# probe.net
KiCad netlist of a schematic drawn in EAGLE
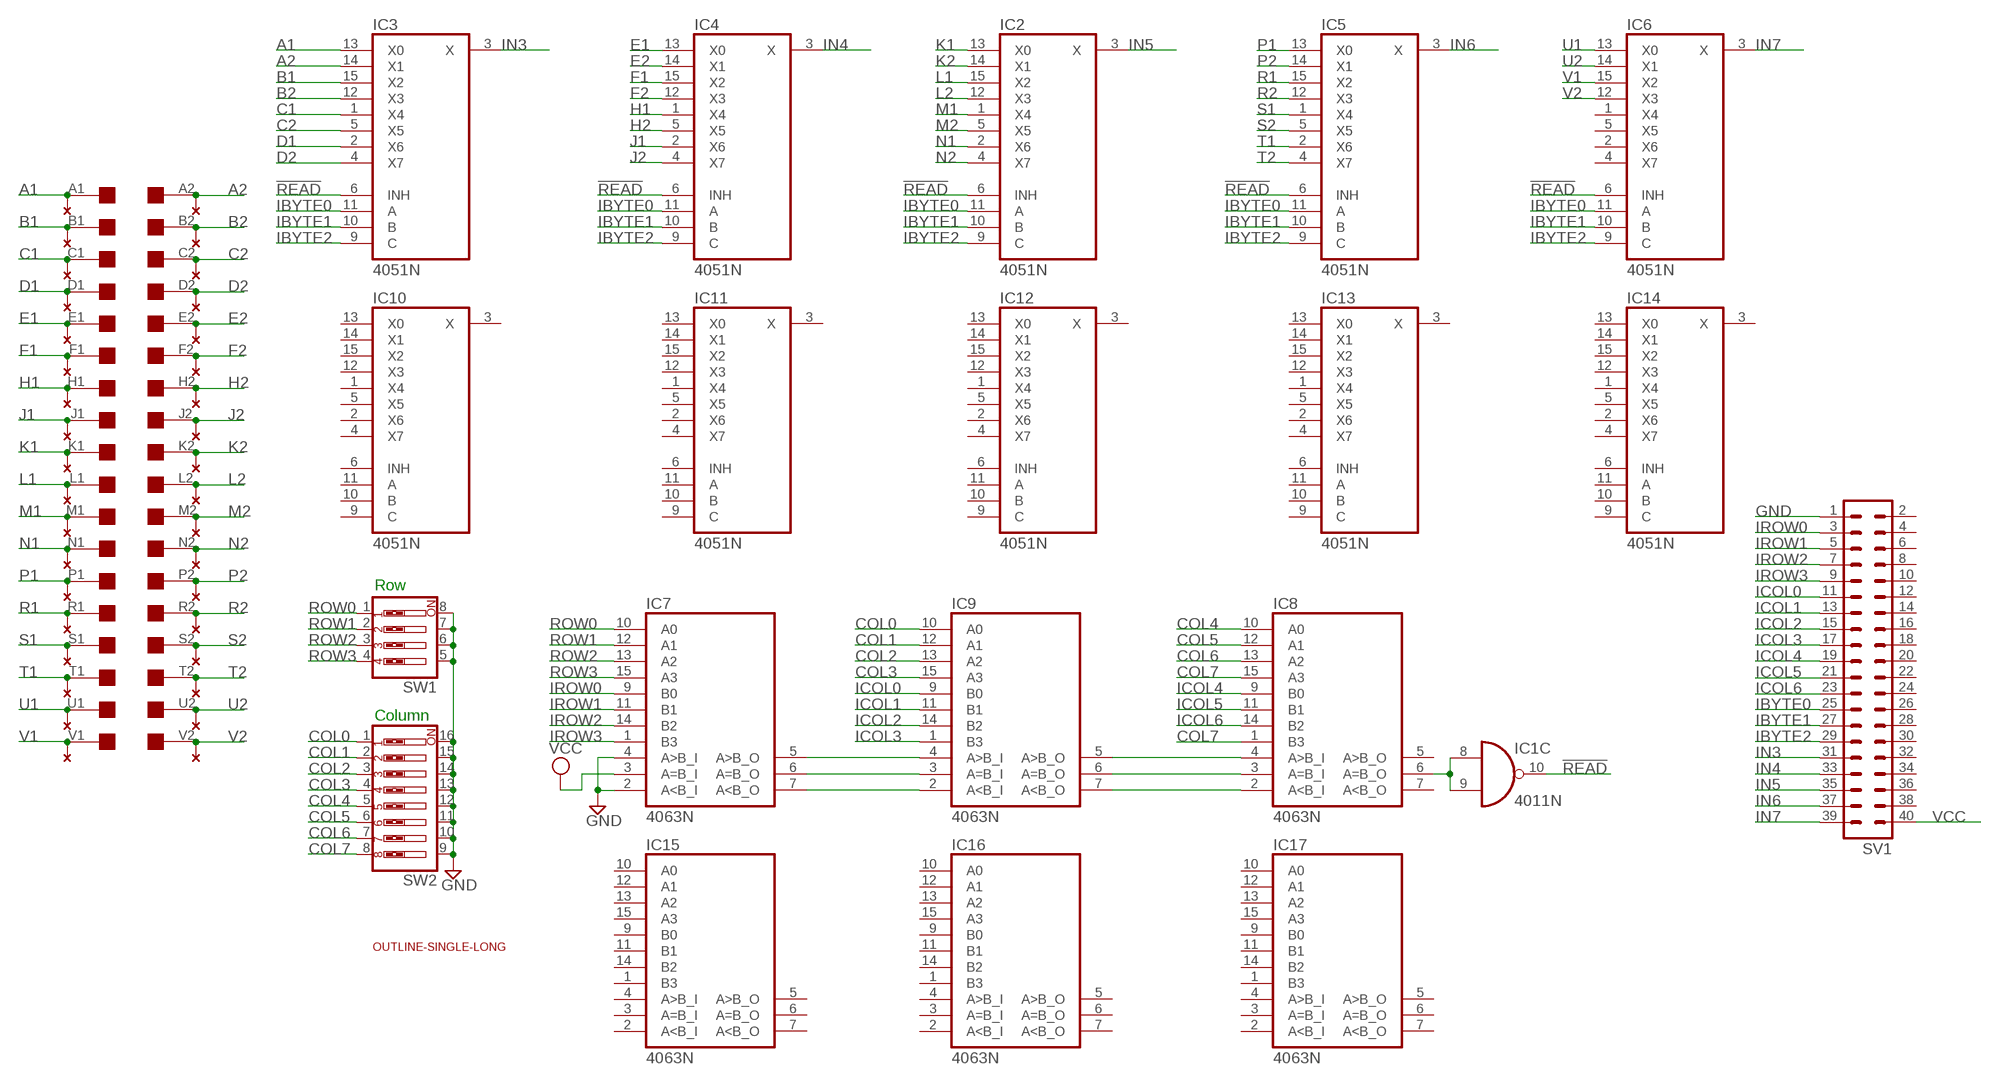
[diagram p0: schematic, sheet 1]

(export (version "E")
  (design (tool "Eeschema 10.0.6"))
  (components
    (comp (ref "EDGE1")
      (value "EDGE-2CONNECTOR")
      (footprint "eagle-import:EDGE-CON2")
      (libsource (lib "eagle-import") (part "EDGE-2CONNECTOR"))
    )
    (comp (ref "IC1")
      (value "4011N")
      (footprint "eagle-import:DIL14")
      (libsource (lib "eagle-import") (part "4011N"))
    )
    (comp (ref "IC2")
      (value "4051N")
      (footprint "eagle-import:DIL16")
      (libsource (lib "eagle-import") (part "4051N"))
    )
    (comp (ref "IC3")
      (value "4051N")
      (footprint "eagle-import:DIL16")
      (libsource (lib "eagle-import") (part "4051N"))
    )
    (comp (ref "IC4")
      (value "4051N")
      (footprint "eagle-import:DIL16")
      (libsource (lib "eagle-import") (part "4051N"))
    )
    (comp (ref "IC5")
      (value "4051N")
      (footprint "eagle-import:DIL16")
      (libsource (lib "eagle-import") (part "4051N"))
    )
    (comp (ref "IC6")
      (value "4051N")
      (footprint "eagle-import:DIL16")
      (libsource (lib "eagle-import") (part "4051N"))
    )
    (comp (ref "IC7")
      (value "4063N")
      (footprint "eagle-import:DIL16")
      (libsource (lib "eagle-import") (part "4063N"))
    )
    (comp (ref "IC8")
      (value "4063N")
      (footprint "eagle-import:DIL16")
      (libsource (lib "eagle-import") (part "4063N"))
    )
    (comp (ref "IC9")
      (value "4063N")
      (footprint "eagle-import:DIL16")
      (libsource (lib "eagle-import") (part "4063N"))
    )
    (comp (ref "IC10")
      (value "4051N")
      (footprint "eagle-import:DIL16")
      (libsource (lib "eagle-import") (part "4051N"))
    )
    (comp (ref "IC11")
      (value "4051N")
      (footprint "eagle-import:DIL16")
      (libsource (lib "eagle-import") (part "4051N"))
    )
    (comp (ref "IC12")
      (value "4051N")
      (footprint "eagle-import:DIL16")
      (libsource (lib "eagle-import") (part "4051N"))
    )
    (comp (ref "IC13")
      (value "4051N")
      (footprint "eagle-import:DIL16")
      (libsource (lib "eagle-import") (part "4051N"))
    )
    (comp (ref "IC14")
      (value "4051N")
      (footprint "eagle-import:DIL16")
      (libsource (lib "eagle-import") (part "4051N"))
    )
    (comp (ref "IC15")
      (value "4063N")
      (footprint "eagle-import:DIL16")
      (libsource (lib "eagle-import") (part "4063N"))
    )
    (comp (ref "IC16")
      (value "4063N")
      (footprint "eagle-import:DIL16")
      (libsource (lib "eagle-import") (part "4063N"))
    )
    (comp (ref "IC17")
      (value "4063N")
      (footprint "eagle-import:DIL16")
      (libsource (lib "eagle-import") (part "4063N"))
    )
    (comp (ref "SV1")
      (value "MA20-2")
      (footprint "eagle-import:MA20-2")
      (libsource (lib "eagle-import") (part "MA20-2"))
    )
    (comp (ref "SW1")
      (value "SW_DIP-4")
      (footprint "eagle-import:EDG-04")
      (libsource (lib "eagle-import") (part "SW_DIP-4"))
    )
    (comp (ref "SW2")
      (value "SW_DIP-8")
      (footprint "eagle-import:EDG-08")
      (libsource (lib "eagle-import") (part "SW_DIP-8"))
    )
    (comp (ref "U$1")
      (value "OUTLINE-SINGLE-LONG")
      (footprint "eagle-import:SINGLE-LONG")
      (libsource (lib "eagle-import") (part "OUTLINE-SINGLE-LONG"))
    )
    (comp (ref "U$3")
      (value "THRU-HOLE2")
      (footprint "eagle-import:THRU-HOLEB")
      (libsource (lib "eagle-import") (part "THRU-HOLE2"))
    )
  )
  (nets
    (net (code "1") (name "/A1") (class "Default")
      (node (ref "EDGE1") (pin "A1") (pinfunction "1_A1") (pintype "bidirectional"))
      (node (ref "IC3") (pin "13") (pinfunction "X0_13") (pintype "bidirectional"))
      (node (ref "U$3") (pin "A1") (pinfunction "P$1_A1") (pintype "passive"))
    )
    (net (code "2") (name "/A2") (class "Default")
      (node (ref "EDGE1") (pin "A2") (pinfunction "1_A2") (pintype "bidirectional"))
      (node (ref "IC3") (pin "14") (pinfunction "X1_14") (pintype "bidirectional"))
      (node (ref "U$3") (pin "A2") (pinfunction "P$1_A2") (pintype "passive"))
    )
    (net (code "3") (name "/B1") (class "Default")
      (node (ref "EDGE1") (pin "B1") (pinfunction "1_B1") (pintype "bidirectional"))
      (node (ref "IC3") (pin "15") (pinfunction "X2_15") (pintype "bidirectional"))
      (node (ref "U$3") (pin "B1") (pinfunction "P$1_B1") (pintype "passive"))
    )
    (net (code "4") (name "/B2") (class "Default")
      (node (ref "EDGE1") (pin "B2") (pinfunction "1_B2") (pintype "bidirectional"))
      (node (ref "IC3") (pin "12") (pinfunction "X3_12") (pintype "bidirectional"))
      (node (ref "U$3") (pin "B2") (pinfunction "P$1_B2") (pintype "passive"))
    )
    (net (code "5") (name "/C1") (class "Default")
      (node (ref "EDGE1") (pin "C1") (pinfunction "1_C1") (pintype "bidirectional"))
      (node (ref "IC3") (pin "1") (pinfunction "X4_1") (pintype "bidirectional"))
      (node (ref "U$3") (pin "C1") (pinfunction "P$1_C1") (pintype "passive"))
    )
    (net (code "6") (name "/C2") (class "Default")
      (node (ref "EDGE1") (pin "C2") (pinfunction "1_C2") (pintype "bidirectional"))
      (node (ref "IC3") (pin "5") (pinfunction "X5_5") (pintype "bidirectional"))
      (node (ref "U$3") (pin "C2") (pinfunction "P$1_C2") (pintype "passive"))
    )
    (net (code "7") (name "/COL0") (class "Default")
      (node (ref "IC9") (pin "10") (pinfunction "A0_10") (pintype "input"))
      (node (ref "SW2") (pin "1") (pinfunction "1_1") (pintype "passive"))
    )
    (net (code "8") (name "/COL1") (class "Default")
      (node (ref "IC9") (pin "12") (pinfunction "A1_12") (pintype "input"))
      (node (ref "SW2") (pin "2") (pinfunction "2_2") (pintype "passive"))
    )
    (net (code "9") (name "/COL2") (class "Default")
      (node (ref "IC9") (pin "13") (pinfunction "A2_13") (pintype "input"))
      (node (ref "SW2") (pin "3") (pinfunction "3_3") (pintype "passive"))
    )
    (net (code "10") (name "/COL3") (class "Default")
      (node (ref "IC9") (pin "15") (pinfunction "A3_15") (pintype "input"))
      (node (ref "SW2") (pin "4") (pinfunction "4_4") (pintype "passive"))
    )
    (net (code "11") (name "/COL4") (class "Default")
      (node (ref "IC8") (pin "10") (pinfunction "A0_10") (pintype "input"))
      (node (ref "SW2") (pin "5") (pinfunction "5_5") (pintype "passive"))
    )
    (net (code "12") (name "/COL5") (class "Default")
      (node (ref "IC8") (pin "12") (pinfunction "A1_12") (pintype "input"))
      (node (ref "SW2") (pin "6") (pinfunction "6_6") (pintype "passive"))
    )
    (net (code "13") (name "/COL6") (class "Default")
      (node (ref "IC8") (pin "13") (pinfunction "A2_13") (pintype "input"))
      (node (ref "SW2") (pin "7") (pinfunction "7_7") (pintype "passive"))
    )
    (net (code "14") (name "/COL7") (class "Default")
      (node (ref "IC8") (pin "1") (pinfunction "B3_1") (pintype "input"))
      (node (ref "IC8") (pin "15") (pinfunction "A3_15") (pintype "input"))
      (node (ref "SW2") (pin "8") (pinfunction "8_8") (pintype "passive"))
    )
    (net (code "15") (name "/D1") (class "Default")
      (node (ref "EDGE1") (pin "D1") (pinfunction "1_D1") (pintype "bidirectional"))
      (node (ref "IC3") (pin "2") (pinfunction "X6_2") (pintype "bidirectional"))
      (node (ref "U$3") (pin "D1") (pinfunction "P$1_D1") (pintype "passive"))
    )
    (net (code "16") (name "/D2") (class "Default")
      (node (ref "EDGE1") (pin "D2") (pinfunction "1_D2") (pintype "bidirectional"))
      (node (ref "IC3") (pin "4") (pinfunction "X7_4") (pintype "bidirectional"))
      (node (ref "U$3") (pin "D2") (pinfunction "P$1_D2") (pintype "passive"))
    )
    (net (code "17") (name "/E1") (class "Default")
      (node (ref "EDGE1") (pin "E1") (pinfunction "1_E1") (pintype "bidirectional"))
      (node (ref "IC4") (pin "13") (pinfunction "X0_13") (pintype "bidirectional"))
      (node (ref "U$3") (pin "E1") (pinfunction "P$1_E1") (pintype "passive"))
    )
    (net (code "18") (name "/E2") (class "Default")
      (node (ref "EDGE1") (pin "E2") (pinfunction "1_E2") (pintype "bidirectional"))
      (node (ref "IC4") (pin "14") (pinfunction "X1_14") (pintype "bidirectional"))
      (node (ref "U$3") (pin "E2") (pinfunction "P$1_E2") (pintype "passive"))
    )
    (net (code "19") (name "/F1") (class "Default")
      (node (ref "EDGE1") (pin "F1") (pinfunction "1_F1") (pintype "bidirectional"))
      (node (ref "IC4") (pin "15") (pinfunction "X2_15") (pintype "bidirectional"))
      (node (ref "U$3") (pin "F1") (pinfunction "P$1_F1") (pintype "passive"))
    )
    (net (code "20") (name "/F2") (class "Default")
      (node (ref "EDGE1") (pin "F2") (pinfunction "1_F2") (pintype "bidirectional"))
      (node (ref "IC4") (pin "12") (pinfunction "X3_12") (pintype "bidirectional"))
      (node (ref "U$3") (pin "F2") (pinfunction "P$1_F2") (pintype "passive"))
    )
    (net (code "21") (name "/H1") (class "Default")
      (node (ref "EDGE1") (pin "H1") (pinfunction "1_H1") (pintype "bidirectional"))
      (node (ref "IC4") (pin "1") (pinfunction "X4_1") (pintype "bidirectional"))
      (node (ref "U$3") (pin "H1") (pinfunction "P$1_H1") (pintype "passive"))
    )
    (net (code "22") (name "/H2") (class "Default")
      (node (ref "EDGE1") (pin "H2") (pinfunction "1_H2") (pintype "bidirectional"))
      (node (ref "IC4") (pin "5") (pinfunction "X5_5") (pintype "bidirectional"))
      (node (ref "U$3") (pin "H2") (pinfunction "P$1_H2") (pintype "passive"))
    )
    (net (code "23") (name "/IBYTE0") (class "Default")
      (node (ref "IC2") (pin "11") (pinfunction "A_11") (pintype "input"))
      (node (ref "IC3") (pin "11") (pinfunction "A_11") (pintype "input"))
      (node (ref "IC4") (pin "11") (pinfunction "A_11") (pintype "input"))
      (node (ref "IC5") (pin "11") (pinfunction "A_11") (pintype "input"))
      (node (ref "IC6") (pin "11") (pinfunction "A_11") (pintype "input"))
      (node (ref "SV1") (pin "25") (pinfunction "25_25") (pintype "passive"))
    )
    (net (code "24") (name "/IBYTE1") (class "Default")
      (node (ref "IC2") (pin "10") (pinfunction "B_10") (pintype "input"))
      (node (ref "IC3") (pin "10") (pinfunction "B_10") (pintype "input"))
      (node (ref "IC4") (pin "10") (pinfunction "B_10") (pintype "input"))
      (node (ref "IC5") (pin "10") (pinfunction "B_10") (pintype "input"))
      (node (ref "IC6") (pin "10") (pinfunction "B_10") (pintype "input"))
      (node (ref "SV1") (pin "27") (pinfunction "27_27") (pintype "passive"))
    )
    (net (code "25") (name "/IBYTE2") (class "Default")
      (node (ref "IC2") (pin "9") (pinfunction "C_9") (pintype "input"))
      (node (ref "IC3") (pin "9") (pinfunction "C_9") (pintype "input"))
      (node (ref "IC4") (pin "9") (pinfunction "C_9") (pintype "input"))
      (node (ref "IC5") (pin "9") (pinfunction "C_9") (pintype "input"))
      (node (ref "IC6") (pin "9") (pinfunction "C_9") (pintype "input"))
      (node (ref "SV1") (pin "29") (pinfunction "29_29") (pintype "passive"))
    )
    (net (code "26") (name "/ICOL0") (class "Default")
      (node (ref "IC9") (pin "9") (pinfunction "B0_9") (pintype "input"))
      (node (ref "SV1") (pin "11") (pinfunction "11_11") (pintype "passive"))
    )
    (net (code "27") (name "/ICOL1") (class "Default")
      (node (ref "IC9") (pin "11") (pinfunction "B1_11") (pintype "input"))
      (node (ref "SV1") (pin "13") (pinfunction "13_13") (pintype "passive"))
    )
    (net (code "28") (name "/ICOL2") (class "Default")
      (node (ref "IC9") (pin "14") (pinfunction "B2_14") (pintype "input"))
      (node (ref "SV1") (pin "15") (pinfunction "15_15") (pintype "passive"))
    )
    (net (code "29") (name "/ICOL3") (class "Default")
      (node (ref "IC9") (pin "1") (pinfunction "B3_1") (pintype "input"))
      (node (ref "SV1") (pin "17") (pinfunction "17_17") (pintype "passive"))
    )
    (net (code "30") (name "/ICOL4") (class "Default")
      (node (ref "IC8") (pin "9") (pinfunction "B0_9") (pintype "input"))
      (node (ref "SV1") (pin "19") (pinfunction "19_19") (pintype "passive"))
    )
    (net (code "31") (name "/ICOL5") (class "Default")
      (node (ref "IC8") (pin "11") (pinfunction "B1_11") (pintype "input"))
      (node (ref "SV1") (pin "21") (pinfunction "21_21") (pintype "passive"))
    )
    (net (code "32") (name "/ICOL6") (class "Default")
      (node (ref "IC8") (pin "14") (pinfunction "B2_14") (pintype "input"))
      (node (ref "SV1") (pin "23") (pinfunction "23_23") (pintype "passive"))
    )
    (net (code "33") (name "/IN3") (class "Default")
      (node (ref "IC3") (pin "3") (pinfunction "X_3") (pintype "bidirectional"))
      (node (ref "SV1") (pin "31") (pinfunction "31_31") (pintype "passive"))
    )
    (net (code "34") (name "/IN4") (class "Default")
      (node (ref "IC4") (pin "3") (pinfunction "X_3") (pintype "bidirectional"))
      (node (ref "SV1") (pin "33") (pinfunction "33_33") (pintype "passive"))
    )
    (net (code "35") (name "/IN5") (class "Default")
      (node (ref "IC2") (pin "3") (pinfunction "X_3") (pintype "bidirectional"))
      (node (ref "SV1") (pin "35") (pinfunction "35_35") (pintype "passive"))
    )
    (net (code "36") (name "/IN6") (class "Default")
      (node (ref "IC5") (pin "3") (pinfunction "X_3") (pintype "bidirectional"))
      (node (ref "SV1") (pin "37") (pinfunction "37_37") (pintype "passive"))
    )
    (net (code "37") (name "/IN7") (class "Default")
      (node (ref "IC6") (pin "3") (pinfunction "X_3") (pintype "bidirectional"))
      (node (ref "SV1") (pin "39") (pinfunction "39_39") (pintype "passive"))
    )
    (net (code "38") (name "/IROW0") (class "Default")
      (node (ref "IC7") (pin "9") (pinfunction "B0_9") (pintype "input"))
      (node (ref "SV1") (pin "3") (pinfunction "3_3") (pintype "passive"))
    )
    (net (code "39") (name "/IROW1") (class "Default")
      (node (ref "IC7") (pin "11") (pinfunction "B1_11") (pintype "input"))
      (node (ref "SV1") (pin "5") (pinfunction "5_5") (pintype "passive"))
    )
    (net (code "40") (name "/IROW2") (class "Default")
      (node (ref "IC7") (pin "14") (pinfunction "B2_14") (pintype "input"))
      (node (ref "SV1") (pin "7") (pinfunction "7_7") (pintype "passive"))
    )
    (net (code "41") (name "/IROW3") (class "Default")
      (node (ref "IC7") (pin "1") (pinfunction "B3_1") (pintype "input"))
      (node (ref "SV1") (pin "9") (pinfunction "9_9") (pintype "passive"))
    )
    (net (code "42") (name "/J1") (class "Default")
      (node (ref "EDGE1") (pin "J1") (pinfunction "1_J1") (pintype "bidirectional"))
      (node (ref "IC4") (pin "2") (pinfunction "X6_2") (pintype "bidirectional"))
      (node (ref "U$3") (pin "J1") (pinfunction "P$1_J1") (pintype "passive"))
    )
    (net (code "43") (name "/J2") (class "Default")
      (node (ref "EDGE1") (pin "J2") (pinfunction "1_J2") (pintype "bidirectional"))
      (node (ref "IC4") (pin "4") (pinfunction "X7_4") (pintype "bidirectional"))
      (node (ref "U$3") (pin "J2") (pinfunction "P$1_J2") (pintype "passive"))
    )
    (net (code "44") (name "/K1") (class "Default")
      (node (ref "EDGE1") (pin "K1") (pinfunction "1_K1") (pintype "bidirectional"))
      (node (ref "IC2") (pin "13") (pinfunction "X0_13") (pintype "bidirectional"))
      (node (ref "U$3") (pin "K1") (pinfunction "P$1_K1") (pintype "passive"))
    )
    (net (code "45") (name "/K2") (class "Default")
      (node (ref "EDGE1") (pin "K2") (pinfunction "1_K2") (pintype "bidirectional"))
      (node (ref "IC2") (pin "14") (pinfunction "X1_14") (pintype "bidirectional"))
      (node (ref "U$3") (pin "K2") (pinfunction "P$1_K2") (pintype "passive"))
    )
    (net (code "46") (name "/L1") (class "Default")
      (node (ref "EDGE1") (pin "L1") (pinfunction "1_L1") (pintype "bidirectional"))
      (node (ref "IC2") (pin "15") (pinfunction "X2_15") (pintype "bidirectional"))
      (node (ref "U$3") (pin "L1") (pinfunction "P$1_L1") (pintype "passive"))
    )
    (net (code "47") (name "/L2") (class "Default")
      (node (ref "EDGE1") (pin "L2") (pinfunction "1_L2") (pintype "bidirectional"))
      (node (ref "IC2") (pin "12") (pinfunction "X3_12") (pintype "bidirectional"))
      (node (ref "U$3") (pin "L2") (pinfunction "P$1_L2") (pintype "passive"))
    )
    (net (code "48") (name "/M1") (class "Default")
      (node (ref "EDGE1") (pin "M1") (pinfunction "1_M1") (pintype "bidirectional"))
      (node (ref "IC2") (pin "1") (pinfunction "X4_1") (pintype "bidirectional"))
      (node (ref "U$3") (pin "M1") (pinfunction "P$1_M1") (pintype "passive"))
    )
    (net (code "49") (name "/M2") (class "Default")
      (node (ref "EDGE1") (pin "M2") (pinfunction "1_M2") (pintype "bidirectional"))
      (node (ref "IC2") (pin "5") (pinfunction "X5_5") (pintype "bidirectional"))
      (node (ref "U$3") (pin "M2") (pinfunction "P$1_M2") (pintype "passive"))
    )
    (net (code "50") (name "/N1") (class "Default")
      (node (ref "EDGE1") (pin "N1") (pinfunction "1_N1") (pintype "bidirectional"))
      (node (ref "IC2") (pin "2") (pinfunction "X6_2") (pintype "bidirectional"))
      (node (ref "U$3") (pin "N1") (pinfunction "P$1_N1") (pintype "passive"))
    )
    (net (code "51") (name "/N2") (class "Default")
      (node (ref "EDGE1") (pin "N2") (pinfunction "1_N2") (pintype "bidirectional"))
      (node (ref "IC2") (pin "4") (pinfunction "X7_4") (pintype "bidirectional"))
      (node (ref "U$3") (pin "N2") (pinfunction "P$1_N2") (pintype "passive"))
    )
    (net (code "52") (name "/P1") (class "Default")
      (node (ref "EDGE1") (pin "P1") (pinfunction "1_P1") (pintype "bidirectional"))
      (node (ref "IC5") (pin "13") (pinfunction "X0_13") (pintype "bidirectional"))
      (node (ref "U$3") (pin "P1") (pinfunction "P$1_P1") (pintype "passive"))
    )
    (net (code "53") (name "/P2") (class "Default")
      (node (ref "EDGE1") (pin "P2") (pinfunction "1_P2") (pintype "bidirectional"))
      (node (ref "IC5") (pin "14") (pinfunction "X1_14") (pintype "bidirectional"))
      (node (ref "U$3") (pin "P2") (pinfunction "P$1_P2") (pintype "passive"))
    )
    (net (code "54") (name "/R1") (class "Default")
      (node (ref "EDGE1") (pin "R1") (pinfunction "1_R1") (pintype "bidirectional"))
      (node (ref "IC5") (pin "15") (pinfunction "X2_15") (pintype "bidirectional"))
      (node (ref "U$3") (pin "R1") (pinfunction "P$1_R1") (pintype "passive"))
    )
    (net (code "55") (name "/R2") (class "Default")
      (node (ref "EDGE1") (pin "R2") (pinfunction "1_R2") (pintype "bidirectional"))
      (node (ref "IC5") (pin "12") (pinfunction "X3_12") (pintype "bidirectional"))
      (node (ref "U$3") (pin "R2") (pinfunction "P$1_R2") (pintype "passive"))
    )
    (net (code "56") (name "/ROW0") (class "Default")
      (node (ref "IC7") (pin "10") (pinfunction "A0_10") (pintype "input"))
      (node (ref "SW1") (pin "1") (pinfunction "1_1") (pintype "passive"))
    )
    (net (code "57") (name "/ROW1") (class "Default")
      (node (ref "IC7") (pin "12") (pinfunction "A1_12") (pintype "input"))
      (node (ref "SW1") (pin "2") (pinfunction "2_2") (pintype "passive"))
    )
    (net (code "58") (name "/ROW2") (class "Default")
      (node (ref "IC7") (pin "13") (pinfunction "A2_13") (pintype "input"))
      (node (ref "SW1") (pin "3") (pinfunction "3_3") (pintype "passive"))
    )
    (net (code "59") (name "/ROW3") (class "Default")
      (node (ref "IC7") (pin "15") (pinfunction "A3_15") (pintype "input"))
      (node (ref "SW1") (pin "4") (pinfunction "4_4") (pintype "passive"))
    )
    (net (code "60") (name "/S1") (class "Default")
      (node (ref "EDGE1") (pin "S1") (pinfunction "1_S1") (pintype "bidirectional"))
      (node (ref "IC5") (pin "1") (pinfunction "X4_1") (pintype "bidirectional"))
      (node (ref "U$3") (pin "S1") (pinfunction "P$1_S1") (pintype "passive"))
    )
    (net (code "61") (name "/S2") (class "Default")
      (node (ref "EDGE1") (pin "S2") (pinfunction "1_S2") (pintype "bidirectional"))
      (node (ref "IC5") (pin "5") (pinfunction "X5_5") (pintype "bidirectional"))
      (node (ref "U$3") (pin "S2") (pinfunction "P$1_S2") (pintype "passive"))
    )
    (net (code "62") (name "/T1") (class "Default")
      (node (ref "EDGE1") (pin "T1") (pinfunction "1_T1") (pintype "bidirectional"))
      (node (ref "IC5") (pin "2") (pinfunction "X6_2") (pintype "bidirectional"))
      (node (ref "U$3") (pin "T1") (pinfunction "P$1_T1") (pintype "passive"))
    )
    (net (code "63") (name "/T2") (class "Default")
      (node (ref "EDGE1") (pin "T2") (pinfunction "1_T2") (pintype "bidirectional"))
      (node (ref "IC5") (pin "4") (pinfunction "X7_4") (pintype "bidirectional"))
      (node (ref "U$3") (pin "T2") (pinfunction "P$1_T2") (pintype "passive"))
    )
    (net (code "64") (name "/U1") (class "Default")
      (node (ref "EDGE1") (pin "U1") (pinfunction "1_U1") (pintype "bidirectional"))
      (node (ref "IC6") (pin "13") (pinfunction "X0_13") (pintype "bidirectional"))
      (node (ref "U$3") (pin "U1") (pinfunction "P$1_U1") (pintype "passive"))
    )
    (net (code "65") (name "/U2") (class "Default")
      (node (ref "EDGE1") (pin "U2") (pinfunction "1_U2") (pintype "bidirectional"))
      (node (ref "IC6") (pin "14") (pinfunction "X1_14") (pintype "bidirectional"))
      (node (ref "U$3") (pin "U2") (pinfunction "P$1_U2") (pintype "passive"))
    )
    (net (code "66") (name "/V1") (class "Default")
      (node (ref "EDGE1") (pin "V1") (pinfunction "1_V1") (pintype "bidirectional"))
      (node (ref "IC6") (pin "15") (pinfunction "X2_15") (pintype "bidirectional"))
      (node (ref "U$3") (pin "V1") (pinfunction "P$1_V1") (pintype "passive"))
    )
    (net (code "67") (name "/V2") (class "Default")
      (node (ref "EDGE1") (pin "V2") (pinfunction "1_V2") (pintype "bidirectional"))
      (node (ref "IC6") (pin "12") (pinfunction "X3_12") (pintype "bidirectional"))
      (node (ref "U$3") (pin "V2") (pinfunction "P$1_V2") (pintype "passive"))
    )
    (net (code "68") (name "/~{READ}") (class "Default")
      (node (ref "IC1") (pin "10") (pinfunction "O_10") (pintype "output"))
      (node (ref "IC2") (pin "6") (pinfunction "INH_6") (pintype "input"))
      (node (ref "IC3") (pin "6") (pinfunction "INH_6") (pintype "input"))
      (node (ref "IC4") (pin "6") (pinfunction "INH_6") (pintype "input"))
      (node (ref "IC5") (pin "6") (pinfunction "INH_6") (pintype "input"))
      (node (ref "IC6") (pin "6") (pinfunction "INH_6") (pintype "input"))
    )
    (net (code "69") (name "GND") (class "Default")
      (node (ref "IC7") (pin "2") (pinfunction "A<B_I_2") (pintype "input"))
      (node (ref "IC7") (pin "4") (pinfunction "A>B_I_4") (pintype "input"))
      (node (ref "SV1") (pin "1") (pinfunction "1_1") (pintype "passive"))
      (node (ref "SW1") (pin "5") (pinfunction "5_5") (pintype "passive"))
      (node (ref "SW1") (pin "6") (pinfunction "6_6") (pintype "passive"))
      (node (ref "SW1") (pin "7") (pinfunction "7_7") (pintype "passive"))
      (node (ref "SW1") (pin "8") (pinfunction "8_8") (pintype "passive"))
      (node (ref "SW2") (pin "10") (pinfunction "10_10") (pintype "passive"))
      (node (ref "SW2") (pin "11") (pinfunction "11_11") (pintype "passive"))
      (node (ref "SW2") (pin "12") (pinfunction "12_12") (pintype "passive"))
      (node (ref "SW2") (pin "13") (pinfunction "13_13") (pintype "passive"))
      (node (ref "SW2") (pin "14") (pinfunction "14_14") (pintype "passive"))
      (node (ref "SW2") (pin "15") (pinfunction "15_15") (pintype "passive"))
      (node (ref "SW2") (pin "16") (pinfunction "16_16") (pintype "passive"))
      (node (ref "SW2") (pin "9") (pinfunction "9_9") (pintype "passive"))
    )
    (net (code "70") (name "Net-(IC1C-I0)") (class "Default")
      (node (ref "IC1") (pin "8") (pinfunction "I0_8") (pintype "input"))
      (node (ref "IC1") (pin "9") (pinfunction "I1_9") (pintype "input"))
      (node (ref "IC8") (pin "6") (pinfunction "A=B_O_6") (pintype "output"))
    )
    (net (code "71") (name "Net-(IC7A-A<B_O)") (class "Default")
      (node (ref "IC7") (pin "7") (pinfunction "A<B_O_7") (pintype "output"))
      (node (ref "IC9") (pin "2") (pinfunction "A<B_I_2") (pintype "input"))
    )
    (net (code "72") (name "Net-(IC7A-A=B_O)") (class "Default")
      (node (ref "IC7") (pin "6") (pinfunction "A=B_O_6") (pintype "output"))
      (node (ref "IC9") (pin "3") (pinfunction "A=B_I_3") (pintype "input"))
    )
    (net (code "73") (name "Net-(IC7A-A>B_O)") (class "Default")
      (node (ref "IC7") (pin "5") (pinfunction "A>B_O_5") (pintype "output"))
      (node (ref "IC9") (pin "4") (pinfunction "A>B_I_4") (pintype "input"))
    )
    (net (code "74") (name "Net-(IC8A-A<B_I)") (class "Default")
      (node (ref "IC8") (pin "2") (pinfunction "A<B_I_2") (pintype "input"))
      (node (ref "IC9") (pin "7") (pinfunction "A<B_O_7") (pintype "output"))
    )
    (net (code "75") (name "Net-(IC8A-A=B_I)") (class "Default")
      (node (ref "IC8") (pin "3") (pinfunction "A=B_I_3") (pintype "input"))
      (node (ref "IC9") (pin "6") (pinfunction "A=B_O_6") (pintype "output"))
    )
    (net (code "76") (name "Net-(IC8A-A>B_I)") (class "Default")
      (node (ref "IC8") (pin "4") (pinfunction "A>B_I_4") (pintype "input"))
      (node (ref "IC9") (pin "5") (pinfunction "A>B_O_5") (pintype "output"))
    )
    (net (code "77") (name "VCC") (class "Default")
      (node (ref "IC7") (pin "3") (pinfunction "A=B_I_3") (pintype "input"))
      (node (ref "SV1") (pin "40") (pinfunction "40_40") (pintype "passive"))
    )
    (net (code "78") (name "unconnected-(IC6A-X4-Pad1)") (class "Default")
      (node (ref "IC6") (pin "1") (pinfunction "X4_1") (pintype "bidirectional"))
    )
    (net (code "79") (name "unconnected-(IC6A-X5-Pad5)") (class "Default")
      (node (ref "IC6") (pin "5") (pinfunction "X5_5") (pintype "bidirectional"))
    )
    (net (code "80") (name "unconnected-(IC6A-X6-Pad2)") (class "Default")
      (node (ref "IC6") (pin "2") (pinfunction "X6_2") (pintype "bidirectional"))
    )
    (net (code "81") (name "unconnected-(IC6A-X7-Pad4)") (class "Default")
      (node (ref "IC6") (pin "4") (pinfunction "X7_4") (pintype "bidirectional"))
    )
    (net (code "82") (name "unconnected-(IC8A-A<B_O-Pad7)") (class "Default")
      (node (ref "IC8") (pin "7") (pinfunction "A<B_O_7") (pintype "output"))
    )
    (net (code "83") (name "unconnected-(IC8A-A>B_O-Pad5)") (class "Default")
      (node (ref "IC8") (pin "5") (pinfunction "A>B_O_5") (pintype "output"))
    )
    (net (code "84") (name "unconnected-(IC10A-A-Pad11)") (class "Default")
      (node (ref "IC10") (pin "11") (pinfunction "A_11") (pintype "input"))
    )
    (net (code "85") (name "unconnected-(IC10A-B-Pad10)") (class "Default")
      (node (ref "IC10") (pin "10") (pinfunction "B_10") (pintype "input"))
    )
    (net (code "86") (name "unconnected-(IC10A-C-Pad9)") (class "Default")
      (node (ref "IC10") (pin "9") (pinfunction "C_9") (pintype "input"))
    )
    (net (code "87") (name "unconnected-(IC10A-INH-Pad6)") (class "Default")
      (node (ref "IC10") (pin "6") (pinfunction "INH_6") (pintype "input"))
    )
    (net (code "88") (name "unconnected-(IC10A-X-Pad3)") (class "Default")
      (node (ref "IC10") (pin "3") (pinfunction "X_3") (pintype "bidirectional"))
    )
    (net (code "89") (name "unconnected-(IC10A-X0-Pad13)") (class "Default")
      (node (ref "IC10") (pin "13") (pinfunction "X0_13") (pintype "bidirectional"))
    )
    (net (code "90") (name "unconnected-(IC10A-X1-Pad14)") (class "Default")
      (node (ref "IC10") (pin "14") (pinfunction "X1_14") (pintype "bidirectional"))
    )
    (net (code "91") (name "unconnected-(IC10A-X2-Pad15)") (class "Default")
      (node (ref "IC10") (pin "15") (pinfunction "X2_15") (pintype "bidirectional"))
    )
    (net (code "92") (name "unconnected-(IC10A-X3-Pad12)") (class "Default")
      (node (ref "IC10") (pin "12") (pinfunction "X3_12") (pintype "bidirectional"))
    )
    (net (code "93") (name "unconnected-(IC10A-X4-Pad1)") (class "Default")
      (node (ref "IC10") (pin "1") (pinfunction "X4_1") (pintype "bidirectional"))
    )
    (net (code "94") (name "unconnected-(IC10A-X5-Pad5)") (class "Default")
      (node (ref "IC10") (pin "5") (pinfunction "X5_5") (pintype "bidirectional"))
    )
    (net (code "95") (name "unconnected-(IC10A-X6-Pad2)") (class "Default")
      (node (ref "IC10") (pin "2") (pinfunction "X6_2") (pintype "bidirectional"))
    )
    (net (code "96") (name "unconnected-(IC10A-X7-Pad4)") (class "Default")
      (node (ref "IC10") (pin "4") (pinfunction "X7_4") (pintype "bidirectional"))
    )
    (net (code "97") (name "unconnected-(IC11A-A-Pad11)") (class "Default")
      (node (ref "IC11") (pin "11") (pinfunction "A_11") (pintype "input"))
    )
    (net (code "98") (name "unconnected-(IC11A-B-Pad10)") (class "Default")
      (node (ref "IC11") (pin "10") (pinfunction "B_10") (pintype "input"))
    )
    (net (code "99") (name "unconnected-(IC11A-C-Pad9)") (class "Default")
      (node (ref "IC11") (pin "9") (pinfunction "C_9") (pintype "input"))
    )
    (net (code "100") (name "unconnected-(IC11A-INH-Pad6)") (class "Default")
      (node (ref "IC11") (pin "6") (pinfunction "INH_6") (pintype "input"))
    )
    (net (code "101") (name "unconnected-(IC11A-X-Pad3)") (class "Default")
      (node (ref "IC11") (pin "3") (pinfunction "X_3") (pintype "bidirectional"))
    )
    (net (code "102") (name "unconnected-(IC11A-X0-Pad13)") (class "Default")
      (node (ref "IC11") (pin "13") (pinfunction "X0_13") (pintype "bidirectional"))
    )
    (net (code "103") (name "unconnected-(IC11A-X1-Pad14)") (class "Default")
      (node (ref "IC11") (pin "14") (pinfunction "X1_14") (pintype "bidirectional"))
    )
    (net (code "104") (name "unconnected-(IC11A-X2-Pad15)") (class "Default")
      (node (ref "IC11") (pin "15") (pinfunction "X2_15") (pintype "bidirectional"))
    )
    (net (code "105") (name "unconnected-(IC11A-X3-Pad12)") (class "Default")
      (node (ref "IC11") (pin "12") (pinfunction "X3_12") (pintype "bidirectional"))
    )
    (net (code "106") (name "unconnected-(IC11A-X4-Pad1)") (class "Default")
      (node (ref "IC11") (pin "1") (pinfunction "X4_1") (pintype "bidirectional"))
    )
    (net (code "107") (name "unconnected-(IC11A-X5-Pad5)") (class "Default")
      (node (ref "IC11") (pin "5") (pinfunction "X5_5") (pintype "bidirectional"))
    )
    (net (code "108") (name "unconnected-(IC11A-X6-Pad2)") (class "Default")
      (node (ref "IC11") (pin "2") (pinfunction "X6_2") (pintype "bidirectional"))
    )
    (net (code "109") (name "unconnected-(IC11A-X7-Pad4)") (class "Default")
      (node (ref "IC11") (pin "4") (pinfunction "X7_4") (pintype "bidirectional"))
    )
    (net (code "110") (name "unconnected-(IC12A-A-Pad11)") (class "Default")
      (node (ref "IC12") (pin "11") (pinfunction "A_11") (pintype "input"))
    )
    (net (code "111") (name "unconnected-(IC12A-B-Pad10)") (class "Default")
      (node (ref "IC12") (pin "10") (pinfunction "B_10") (pintype "input"))
    )
    (net (code "112") (name "unconnected-(IC12A-C-Pad9)") (class "Default")
      (node (ref "IC12") (pin "9") (pinfunction "C_9") (pintype "input"))
    )
    (net (code "113") (name "unconnected-(IC12A-INH-Pad6)") (class "Default")
      (node (ref "IC12") (pin "6") (pinfunction "INH_6") (pintype "input"))
    )
    (net (code "114") (name "unconnected-(IC12A-X-Pad3)") (class "Default")
      (node (ref "IC12") (pin "3") (pinfunction "X_3") (pintype "bidirectional"))
    )
    (net (code "115") (name "unconnected-(IC12A-X0-Pad13)") (class "Default")
      (node (ref "IC12") (pin "13") (pinfunction "X0_13") (pintype "bidirectional"))
    )
    (net (code "116") (name "unconnected-(IC12A-X1-Pad14)") (class "Default")
      (node (ref "IC12") (pin "14") (pinfunction "X1_14") (pintype "bidirectional"))
    )
    (net (code "117") (name "unconnected-(IC12A-X2-Pad15)") (class "Default")
      (node (ref "IC12") (pin "15") (pinfunction "X2_15") (pintype "bidirectional"))
    )
    (net (code "118") (name "unconnected-(IC12A-X3-Pad12)") (class "Default")
      (node (ref "IC12") (pin "12") (pinfunction "X3_12") (pintype "bidirectional"))
    )
    (net (code "119") (name "unconnected-(IC12A-X4-Pad1)") (class "Default")
      (node (ref "IC12") (pin "1") (pinfunction "X4_1") (pintype "bidirectional"))
    )
    (net (code "120") (name "unconnected-(IC12A-X5-Pad5)") (class "Default")
      (node (ref "IC12") (pin "5") (pinfunction "X5_5") (pintype "bidirectional"))
    )
    (net (code "121") (name "unconnected-(IC12A-X6-Pad2)") (class "Default")
      (node (ref "IC12") (pin "2") (pinfunction "X6_2") (pintype "bidirectional"))
    )
    (net (code "122") (name "unconnected-(IC12A-X7-Pad4)") (class "Default")
      (node (ref "IC12") (pin "4") (pinfunction "X7_4") (pintype "bidirectional"))
    )
    (net (code "123") (name "unconnected-(IC13A-A-Pad11)") (class "Default")
      (node (ref "IC13") (pin "11") (pinfunction "A_11") (pintype "input"))
    )
    (net (code "124") (name "unconnected-(IC13A-B-Pad10)") (class "Default")
      (node (ref "IC13") (pin "10") (pinfunction "B_10") (pintype "input"))
    )
    (net (code "125") (name "unconnected-(IC13A-C-Pad9)") (class "Default")
      (node (ref "IC13") (pin "9") (pinfunction "C_9") (pintype "input"))
    )
    (net (code "126") (name "unconnected-(IC13A-INH-Pad6)") (class "Default")
      (node (ref "IC13") (pin "6") (pinfunction "INH_6") (pintype "input"))
    )
    (net (code "127") (name "unconnected-(IC13A-X-Pad3)") (class "Default")
      (node (ref "IC13") (pin "3") (pinfunction "X_3") (pintype "bidirectional"))
    )
    (net (code "128") (name "unconnected-(IC13A-X0-Pad13)") (class "Default")
      (node (ref "IC13") (pin "13") (pinfunction "X0_13") (pintype "bidirectional"))
    )
    (net (code "129") (name "unconnected-(IC13A-X1-Pad14)") (class "Default")
      (node (ref "IC13") (pin "14") (pinfunction "X1_14") (pintype "bidirectional"))
    )
    (net (code "130") (name "unconnected-(IC13A-X2-Pad15)") (class "Default")
      (node (ref "IC13") (pin "15") (pinfunction "X2_15") (pintype "bidirectional"))
    )
    (net (code "131") (name "unconnected-(IC13A-X3-Pad12)") (class "Default")
      (node (ref "IC13") (pin "12") (pinfunction "X3_12") (pintype "bidirectional"))
    )
    (net (code "132") (name "unconnected-(IC13A-X4-Pad1)") (class "Default")
      (node (ref "IC13") (pin "1") (pinfunction "X4_1") (pintype "bidirectional"))
    )
    (net (code "133") (name "unconnected-(IC13A-X5-Pad5)") (class "Default")
      (node (ref "IC13") (pin "5") (pinfunction "X5_5") (pintype "bidirectional"))
    )
    (net (code "134") (name "unconnected-(IC13A-X6-Pad2)") (class "Default")
      (node (ref "IC13") (pin "2") (pinfunction "X6_2") (pintype "bidirectional"))
    )
    (net (code "135") (name "unconnected-(IC13A-X7-Pad4)") (class "Default")
      (node (ref "IC13") (pin "4") (pinfunction "X7_4") (pintype "bidirectional"))
    )
    (net (code "136") (name "unconnected-(IC14A-A-Pad11)") (class "Default")
      (node (ref "IC14") (pin "11") (pinfunction "A_11") (pintype "input"))
    )
    (net (code "137") (name "unconnected-(IC14A-B-Pad10)") (class "Default")
      (node (ref "IC14") (pin "10") (pinfunction "B_10") (pintype "input"))
    )
    (net (code "138") (name "unconnected-(IC14A-C-Pad9)") (class "Default")
      (node (ref "IC14") (pin "9") (pinfunction "C_9") (pintype "input"))
    )
    (net (code "139") (name "unconnected-(IC14A-INH-Pad6)") (class "Default")
      (node (ref "IC14") (pin "6") (pinfunction "INH_6") (pintype "input"))
    )
    (net (code "140") (name "unconnected-(IC14A-X-Pad3)") (class "Default")
      (node (ref "IC14") (pin "3") (pinfunction "X_3") (pintype "bidirectional"))
    )
    (net (code "141") (name "unconnected-(IC14A-X0-Pad13)") (class "Default")
      (node (ref "IC14") (pin "13") (pinfunction "X0_13") (pintype "bidirectional"))
    )
    (net (code "142") (name "unconnected-(IC14A-X1-Pad14)") (class "Default")
      (node (ref "IC14") (pin "14") (pinfunction "X1_14") (pintype "bidirectional"))
    )
    (net (code "143") (name "unconnected-(IC14A-X2-Pad15)") (class "Default")
      (node (ref "IC14") (pin "15") (pinfunction "X2_15") (pintype "bidirectional"))
    )
    (net (code "144") (name "unconnected-(IC14A-X3-Pad12)") (class "Default")
      (node (ref "IC14") (pin "12") (pinfunction "X3_12") (pintype "bidirectional"))
    )
    (net (code "145") (name "unconnected-(IC14A-X4-Pad1)") (class "Default")
      (node (ref "IC14") (pin "1") (pinfunction "X4_1") (pintype "bidirectional"))
    )
    (net (code "146") (name "unconnected-(IC14A-X5-Pad5)") (class "Default")
      (node (ref "IC14") (pin "5") (pinfunction "X5_5") (pintype "bidirectional"))
    )
    (net (code "147") (name "unconnected-(IC14A-X6-Pad2)") (class "Default")
      (node (ref "IC14") (pin "2") (pinfunction "X6_2") (pintype "bidirectional"))
    )
    (net (code "148") (name "unconnected-(IC14A-X7-Pad4)") (class "Default")
      (node (ref "IC14") (pin "4") (pinfunction "X7_4") (pintype "bidirectional"))
    )
    (net (code "149") (name "unconnected-(IC15A-A0-Pad10)") (class "Default")
      (node (ref "IC15") (pin "10") (pinfunction "A0_10") (pintype "input"))
    )
    (net (code "150") (name "unconnected-(IC15A-A1-Pad12)") (class "Default")
      (node (ref "IC15") (pin "12") (pinfunction "A1_12") (pintype "input"))
    )
    (net (code "151") (name "unconnected-(IC15A-A2-Pad13)") (class "Default")
      (node (ref "IC15") (pin "13") (pinfunction "A2_13") (pintype "input"))
    )
    (net (code "152") (name "unconnected-(IC15A-A3-Pad15)") (class "Default")
      (node (ref "IC15") (pin "15") (pinfunction "A3_15") (pintype "input"))
    )
    (net (code "153") (name "unconnected-(IC15A-A<B_I-Pad2)") (class "Default")
      (node (ref "IC15") (pin "2") (pinfunction "A<B_I_2") (pintype "input"))
    )
    (net (code "154") (name "unconnected-(IC15A-A<B_O-Pad7)") (class "Default")
      (node (ref "IC15") (pin "7") (pinfunction "A<B_O_7") (pintype "output"))
    )
    (net (code "155") (name "unconnected-(IC15A-A=B_I-Pad3)") (class "Default")
      (node (ref "IC15") (pin "3") (pinfunction "A=B_I_3") (pintype "input"))
    )
    (net (code "156") (name "unconnected-(IC15A-A=B_O-Pad6)") (class "Default")
      (node (ref "IC15") (pin "6") (pinfunction "A=B_O_6") (pintype "output"))
    )
    (net (code "157") (name "unconnected-(IC15A-A>B_I-Pad4)") (class "Default")
      (node (ref "IC15") (pin "4") (pinfunction "A>B_I_4") (pintype "input"))
    )
    (net (code "158") (name "unconnected-(IC15A-A>B_O-Pad5)") (class "Default")
      (node (ref "IC15") (pin "5") (pinfunction "A>B_O_5") (pintype "output"))
    )
    (net (code "159") (name "unconnected-(IC15A-B0-Pad9)") (class "Default")
      (node (ref "IC15") (pin "9") (pinfunction "B0_9") (pintype "input"))
    )
    (net (code "160") (name "unconnected-(IC15A-B1-Pad11)") (class "Default")
      (node (ref "IC15") (pin "11") (pinfunction "B1_11") (pintype "input"))
    )
    (net (code "161") (name "unconnected-(IC15A-B2-Pad14)") (class "Default")
      (node (ref "IC15") (pin "14") (pinfunction "B2_14") (pintype "input"))
    )
    (net (code "162") (name "unconnected-(IC15A-B3-Pad1)") (class "Default")
      (node (ref "IC15") (pin "1") (pinfunction "B3_1") (pintype "input"))
    )
    (net (code "163") (name "unconnected-(IC16A-A0-Pad10)") (class "Default")
      (node (ref "IC16") (pin "10") (pinfunction "A0_10") (pintype "input"))
    )
    (net (code "164") (name "unconnected-(IC16A-A1-Pad12)") (class "Default")
      (node (ref "IC16") (pin "12") (pinfunction "A1_12") (pintype "input"))
    )
    (net (code "165") (name "unconnected-(IC16A-A2-Pad13)") (class "Default")
      (node (ref "IC16") (pin "13") (pinfunction "A2_13") (pintype "input"))
    )
    (net (code "166") (name "unconnected-(IC16A-A3-Pad15)") (class "Default")
      (node (ref "IC16") (pin "15") (pinfunction "A3_15") (pintype "input"))
    )
    (net (code "167") (name "unconnected-(IC16A-A<B_I-Pad2)") (class "Default")
      (node (ref "IC16") (pin "2") (pinfunction "A<B_I_2") (pintype "input"))
    )
    (net (code "168") (name "unconnected-(IC16A-A<B_O-Pad7)") (class "Default")
      (node (ref "IC16") (pin "7") (pinfunction "A<B_O_7") (pintype "output"))
    )
    (net (code "169") (name "unconnected-(IC16A-A=B_I-Pad3)") (class "Default")
      (node (ref "IC16") (pin "3") (pinfunction "A=B_I_3") (pintype "input"))
    )
    (net (code "170") (name "unconnected-(IC16A-A=B_O-Pad6)") (class "Default")
      (node (ref "IC16") (pin "6") (pinfunction "A=B_O_6") (pintype "output"))
    )
    (net (code "171") (name "unconnected-(IC16A-A>B_I-Pad4)") (class "Default")
      (node (ref "IC16") (pin "4") (pinfunction "A>B_I_4") (pintype "input"))
    )
    (net (code "172") (name "unconnected-(IC16A-A>B_O-Pad5)") (class "Default")
      (node (ref "IC16") (pin "5") (pinfunction "A>B_O_5") (pintype "output"))
    )
    (net (code "173") (name "unconnected-(IC16A-B0-Pad9)") (class "Default")
      (node (ref "IC16") (pin "9") (pinfunction "B0_9") (pintype "input"))
    )
    (net (code "174") (name "unconnected-(IC16A-B1-Pad11)") (class "Default")
      (node (ref "IC16") (pin "11") (pinfunction "B1_11") (pintype "input"))
    )
    (net (code "175") (name "unconnected-(IC16A-B2-Pad14)") (class "Default")
      (node (ref "IC16") (pin "14") (pinfunction "B2_14") (pintype "input"))
    )
    (net (code "176") (name "unconnected-(IC16A-B3-Pad1)") (class "Default")
      (node (ref "IC16") (pin "1") (pinfunction "B3_1") (pintype "input"))
    )
    (net (code "177") (name "unconnected-(IC17A-A0-Pad10)") (class "Default")
      (node (ref "IC17") (pin "10") (pinfunction "A0_10") (pintype "input"))
    )
    (net (code "178") (name "unconnected-(IC17A-A1-Pad12)") (class "Default")
      (node (ref "IC17") (pin "12") (pinfunction "A1_12") (pintype "input"))
    )
    (net (code "179") (name "unconnected-(IC17A-A2-Pad13)") (class "Default")
      (node (ref "IC17") (pin "13") (pinfunction "A2_13") (pintype "input"))
    )
    (net (code "180") (name "unconnected-(IC17A-A3-Pad15)") (class "Default")
      (node (ref "IC17") (pin "15") (pinfunction "A3_15") (pintype "input"))
    )
    (net (code "181") (name "unconnected-(IC17A-A<B_I-Pad2)") (class "Default")
      (node (ref "IC17") (pin "2") (pinfunction "A<B_I_2") (pintype "input"))
    )
    (net (code "182") (name "unconnected-(IC17A-A<B_O-Pad7)") (class "Default")
      (node (ref "IC17") (pin "7") (pinfunction "A<B_O_7") (pintype "output"))
    )
    (net (code "183") (name "unconnected-(IC17A-A=B_I-Pad3)") (class "Default")
      (node (ref "IC17") (pin "3") (pinfunction "A=B_I_3") (pintype "input"))
    )
    (net (code "184") (name "unconnected-(IC17A-A=B_O-Pad6)") (class "Default")
      (node (ref "IC17") (pin "6") (pinfunction "A=B_O_6") (pintype "output"))
    )
    (net (code "185") (name "unconnected-(IC17A-A>B_I-Pad4)") (class "Default")
      (node (ref "IC17") (pin "4") (pinfunction "A>B_I_4") (pintype "input"))
    )
    (net (code "186") (name "unconnected-(IC17A-A>B_O-Pad5)") (class "Default")
      (node (ref "IC17") (pin "5") (pinfunction "A>B_O_5") (pintype "output"))
    )
    (net (code "187") (name "unconnected-(IC17A-B0-Pad9)") (class "Default")
      (node (ref "IC17") (pin "9") (pinfunction "B0_9") (pintype "input"))
    )
    (net (code "188") (name "unconnected-(IC17A-B1-Pad11)") (class "Default")
      (node (ref "IC17") (pin "11") (pinfunction "B1_11") (pintype "input"))
    )
    (net (code "189") (name "unconnected-(IC17A-B2-Pad14)") (class "Default")
      (node (ref "IC17") (pin "14") (pinfunction "B2_14") (pintype "input"))
    )
    (net (code "190") (name "unconnected-(IC17A-B3-Pad1)") (class "Default")
      (node (ref "IC17") (pin "1") (pinfunction "B3_1") (pintype "input"))
    )
    (net (code "191") (name "unconnected-(SV1-Pad2)") (class "Default")
      (node (ref "SV1") (pin "2") (pinfunction "2_2") (pintype "passive"))
    )
    (net (code "192") (name "unconnected-(SV1-Pad4)") (class "Default")
      (node (ref "SV1") (pin "4") (pinfunction "4_4") (pintype "passive"))
    )
    (net (code "193") (name "unconnected-(SV1-Pad6)") (class "Default")
      (node (ref "SV1") (pin "6") (pinfunction "6_6") (pintype "passive"))
    )
    (net (code "194") (name "unconnected-(SV1-Pad8)") (class "Default")
      (node (ref "SV1") (pin "8") (pinfunction "8_8") (pintype "passive"))
    )
    (net (code "195") (name "unconnected-(SV1-Pad10)") (class "Default")
      (node (ref "SV1") (pin "10") (pinfunction "10_10") (pintype "passive"))
    )
    (net (code "196") (name "unconnected-(SV1-Pad12)") (class "Default")
      (node (ref "SV1") (pin "12") (pinfunction "12_12") (pintype "passive"))
    )
    (net (code "197") (name "unconnected-(SV1-Pad14)") (class "Default")
      (node (ref "SV1") (pin "14") (pinfunction "14_14") (pintype "passive"))
    )
    (net (code "198") (name "unconnected-(SV1-Pad16)") (class "Default")
      (node (ref "SV1") (pin "16") (pinfunction "16_16") (pintype "passive"))
    )
    (net (code "199") (name "unconnected-(SV1-Pad18)") (class "Default")
      (node (ref "SV1") (pin "18") (pinfunction "18_18") (pintype "passive"))
    )
    (net (code "200") (name "unconnected-(SV1-Pad20)") (class "Default")
      (node (ref "SV1") (pin "20") (pinfunction "20_20") (pintype "passive"))
    )
    (net (code "201") (name "unconnected-(SV1-Pad22)") (class "Default")
      (node (ref "SV1") (pin "22") (pinfunction "22_22") (pintype "passive"))
    )
    (net (code "202") (name "unconnected-(SV1-Pad24)") (class "Default")
      (node (ref "SV1") (pin "24") (pinfunction "24_24") (pintype "passive"))
    )
    (net (code "203") (name "unconnected-(SV1-Pad26)") (class "Default")
      (node (ref "SV1") (pin "26") (pinfunction "26_26") (pintype "passive"))
    )
    (net (code "204") (name "unconnected-(SV1-Pad28)") (class "Default")
      (node (ref "SV1") (pin "28") (pinfunction "28_28") (pintype "passive"))
    )
    (net (code "205") (name "unconnected-(SV1-Pad30)") (class "Default")
      (node (ref "SV1") (pin "30") (pinfunction "30_30") (pintype "passive"))
    )
    (net (code "206") (name "unconnected-(SV1-Pad32)") (class "Default")
      (node (ref "SV1") (pin "32") (pinfunction "32_32") (pintype "passive"))
    )
    (net (code "207") (name "unconnected-(SV1-Pad34)") (class "Default")
      (node (ref "SV1") (pin "34") (pinfunction "34_34") (pintype "passive"))
    )
    (net (code "208") (name "unconnected-(SV1-Pad36)") (class "Default")
      (node (ref "SV1") (pin "36") (pinfunction "36_36") (pintype "passive"))
    )
    (net (code "209") (name "unconnected-(SV1-Pad38)") (class "Default")
      (node (ref "SV1") (pin "38") (pinfunction "38_38") (pintype "passive"))
    )
  )
)
